# mainProbe_ESP12.net
KiCad netlist of a schematic drawn in EAGLE
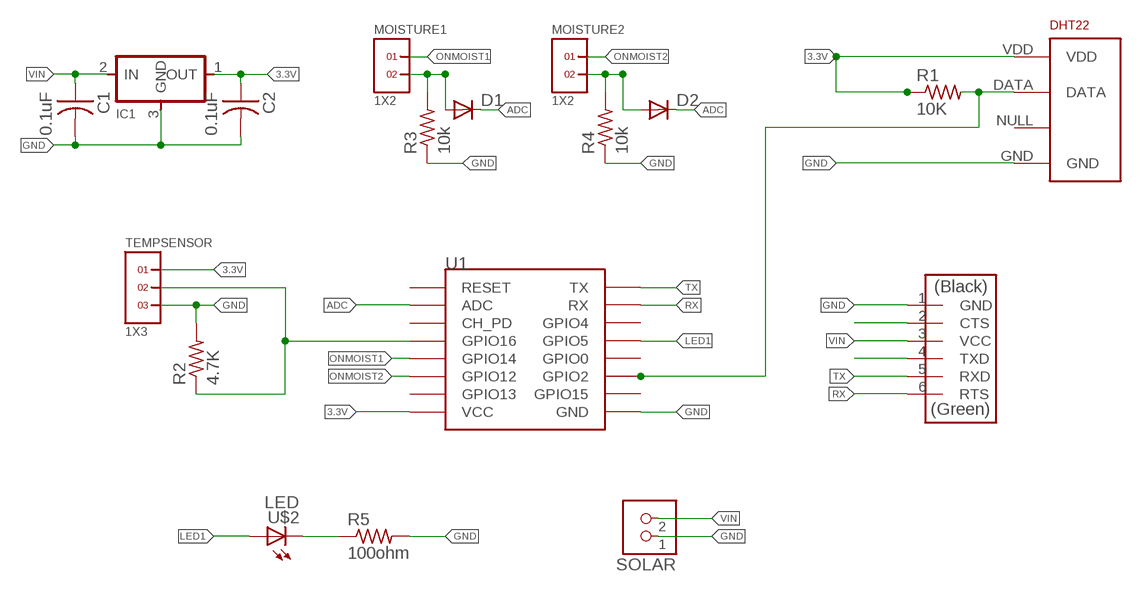
[diagram p0: schematic, sheet 1]

(export (version "E")
  (design (tool "Eeschema 10.0.6"))
  (components
    (comp (ref "C1")
      (value "0.1uF")
      (footprint "eagle-import:C1206")
      (libsource (lib "eagle-import") (part "CAP-US1206"))
    )
    (comp (ref "C2")
      (value "0.1uF")
      (footprint "eagle-import:C1206")
      (libsource (lib "eagle-import") (part "CAP-US1206"))
    )
    (comp (ref "D1")
      (value "DIODESOD123")
      (footprint "eagle-import:SOD123")
      (libsource (lib "eagle-import") (part "DIODESOD123"))
    )
    (comp (ref "D2")
      (value "DIODESOD123")
      (footprint "eagle-import:SOD123")
      (libsource (lib "eagle-import") (part "DIODESOD123"))
    )
    (comp (ref "DHT22")
      (value "RHT03_DHT-22_AM2302")
      (footprint "eagle-import:RHT03_DHT-22")
      (libsource (lib "eagle-import") (part "RHT03_DHT-22_AM2302"))
    )
    (comp (ref "IC1")
      (value "REGULATORSOT23")
      (footprint "eagle-import:SOT23")
      (libsource (lib "eagle-import") (part "REGULATORSOT23"))
    )
    (comp (ref "MOISTURE1")
      (value "1X2")
      (footprint "eagle-import:1X2")
      (libsource (lib "eagle-import") (part "1X2"))
    )
    (comp (ref "MOISTURE2")
      (value "1X2")
      (footprint "eagle-import:1X2")
      (libsource (lib "eagle-import") (part "1X2"))
    )
    (comp (ref "R1")
      (value "10K")
      (footprint "eagle-import:R1206")
      (libsource (lib "eagle-import") (part "RES-US1206"))
    )
    (comp (ref "R2")
      (value "4.7K")
      (footprint "eagle-import:R1206")
      (libsource (lib "eagle-import") (part "RES-US1206"))
    )
    (comp (ref "R3")
      (value "10k")
      (footprint "eagle-import:R1206")
      (libsource (lib "eagle-import") (part "RES-US1206"))
    )
    (comp (ref "R4")
      (value "10k")
      (footprint "eagle-import:R1206")
      (libsource (lib "eagle-import") (part "RES-US1206"))
    )
    (comp (ref "R5")
      (value "100ohm")
      (footprint "eagle-import:R1206")
      (libsource (lib "eagle-import") (part "RES-US1206"))
    )
    (comp (ref "SOLAR")
      (value "TERM-1X02-ADAFRUIT")
      (footprint "eagle-import:3.5MMTERM")
      (libsource (lib "eagle-import") (part "TERM-1X02-ADAFRUIT"))
    )
    (comp (ref "TEMPSENSOR")
      (value "1X3")
      (footprint "eagle-import:1X3")
      (libsource (lib "eagle-import") (part "1X3"))
    )
    (comp (ref "U$1")
      (value "FTDI-SMD-HEADER")
      (footprint "eagle-import:1X06SMD")
      (libsource (lib "eagle-import") (part "FTDI-SMD-HEADER"))
    )
    (comp (ref "U$2")
      (value "LED")
      (footprint "eagle-import:LED1206")
      (libsource (lib "eagle-import") (part "LED"))
    )
    (comp (ref "U1")
      (value "ESP12")
      (footprint "eagle-import:ESP12")
      (libsource (lib "eagle-import") (part "ESP12"))
    )
  )
  (nets
    (net (code "1") (name "3.3V") (class "Default")
      (node (ref "C2") (pin "1") (pinfunction "1_1") (pintype "passive"))
      (node (ref "DHT22") (pin "VDD") (pinfunction "VDD_VDD") (pintype "power_in"))
      (node (ref "IC1") (pin "1") (pinfunction "OUT_1") (pintype "bidirectional"))
      (node (ref "R1") (pin "1") (pinfunction "1_1") (pintype "passive"))
      (node (ref "TEMPSENSOR") (pin "1") (pinfunction "1_1") (pintype "bidirectional"))
      (node (ref "U1") (pin "VCC") (pinfunction "VCC_VCC") (pintype "bidirectional"))
    )
    (net (code "2") (name "ADC") (class "Default")
      (node (ref "D1") (pin "CATHODE") (pinfunction "C_CATHODE") (pintype "passive"))
      (node (ref "D2") (pin "CATHODE") (pinfunction "C_CATHODE") (pintype "passive"))
      (node (ref "U1") (pin "ADC") (pinfunction "ADC_ADC") (pintype "bidirectional"))
    )
    (net (code "3") (name "GND") (class "Default")
      (node (ref "C1") (pin "2") (pinfunction "2_2") (pintype "passive"))
      (node (ref "C2") (pin "2") (pinfunction "2_2") (pintype "passive"))
      (node (ref "DHT22") (pin "GND") (pinfunction "GND_GND") (pintype "power_in"))
      (node (ref "IC1") (pin "3") (pinfunction "GND_3") (pintype "bidirectional"))
      (node (ref "R2") (pin "2") (pinfunction "2_2") (pintype "passive"))
      (node (ref "R3") (pin "1") (pinfunction "1_1") (pintype "passive"))
      (node (ref "R4") (pin "1") (pinfunction "1_1") (pintype "passive"))
      (node (ref "R5") (pin "2") (pinfunction "2_2") (pintype "passive"))
      (node (ref "SOLAR") (pin "1") (pinfunction "1_1") (pintype "passive"))
      (node (ref "TEMPSENSOR") (pin "3") (pinfunction "3_3") (pintype "bidirectional"))
      (node (ref "U$1") (pin "1") (pinfunction "GND_1") (pintype "bidirectional"))
      (node (ref "U1") (pin "GND") (pinfunction "GND_GND") (pintype "bidirectional"))
    )
    (net (code "4") (name "LED1") (class "Default")
      (node (ref "U$2") (pin "1") (pinfunction "A_1") (pintype "passive"))
      (node (ref "U1") (pin "GPIO5") (pinfunction "GPIO5_GPIO5") (pintype "bidirectional"))
    )
    (net (code "5") (name "Net-(D1-A)") (class "Default")
      (node (ref "D1") (pin "ANODE") (pinfunction "A_ANODE") (pintype "passive"))
      (node (ref "MOISTURE1") (pin "2") (pinfunction "2_2") (pintype "bidirectional"))
      (node (ref "R3") (pin "2") (pinfunction "2_2") (pintype "passive"))
    )
    (net (code "6") (name "Net-(D2-A)") (class "Default")
      (node (ref "D2") (pin "ANODE") (pinfunction "A_ANODE") (pintype "passive"))
      (node (ref "MOISTURE2") (pin "2") (pinfunction "2_2") (pintype "bidirectional"))
      (node (ref "R4") (pin "2") (pinfunction "2_2") (pintype "passive"))
    )
    (net (code "7") (name "Net-(DHT22-PadDATA)") (class "Default")
      (node (ref "DHT22") (pin "DATA") (pinfunction "DATA_DATA") (pintype "bidirectional"))
      (node (ref "R1") (pin "2") (pinfunction "2_2") (pintype "passive"))
      (node (ref "U1") (pin "GPIO2") (pinfunction "GPIO2_GPIO2") (pintype "bidirectional"))
    )
    (net (code "8") (name "Net-(R2-Pad1)") (class "Default")
      (node (ref "R2") (pin "1") (pinfunction "1_1") (pintype "passive"))
      (node (ref "TEMPSENSOR") (pin "2") (pinfunction "2_2") (pintype "bidirectional"))
      (node (ref "U1") (pin "GPIO16") (pinfunction "GPIO16_GPIO16") (pintype "bidirectional"))
    )
    (net (code "9") (name "Net-(U$2-C)") (class "Default")
      (node (ref "R5") (pin "1") (pinfunction "1_1") (pintype "passive"))
      (node (ref "U$2") (pin "2") (pinfunction "C_2") (pintype "passive"))
    )
    (net (code "10") (name "ONMOIST1") (class "Default")
      (node (ref "MOISTURE1") (pin "1") (pinfunction "1_1") (pintype "bidirectional"))
      (node (ref "U1") (pin "GPIO14") (pinfunction "GPIO14_GPIO14") (pintype "bidirectional"))
    )
    (net (code "11") (name "ONMOIST2") (class "Default")
      (node (ref "MOISTURE2") (pin "1") (pinfunction "1_1") (pintype "bidirectional"))
      (node (ref "U1") (pin "GPIO12") (pinfunction "GPIO12_GPIO12") (pintype "bidirectional"))
    )
    (net (code "12") (name "RX") (class "Default")
      (node (ref "U$1") (pin "6") (pinfunction "RTS_6") (pintype "bidirectional"))
      (node (ref "U1") (pin "RX") (pinfunction "RX_RX") (pintype "bidirectional"))
    )
    (net (code "13") (name "TX") (class "Default")
      (node (ref "U$1") (pin "5") (pinfunction "RXD_5") (pintype "bidirectional"))
      (node (ref "U1") (pin "TX") (pinfunction "TX_TX") (pintype "bidirectional"))
    )
    (net (code "14") (name "VIN") (class "Default")
      (node (ref "C1") (pin "1") (pinfunction "1_1") (pintype "passive"))
      (node (ref "IC1") (pin "2") (pinfunction "IN_2") (pintype "bidirectional"))
      (node (ref "SOLAR") (pin "2") (pinfunction "2_2") (pintype "passive"))
      (node (ref "U$1") (pin "3") (pinfunction "VCC_3") (pintype "bidirectional"))
    )
    (net (code "15") (name "unconnected-(DHT22-PadNULL)") (class "Default")
      (node (ref "DHT22") (pin "NULL") (pinfunction "NULL_NULL") (pintype "no_connect"))
    )
    (net (code "16") (name "unconnected-(U$1-CTS-Pad2)") (class "Default")
      (node (ref "U$1") (pin "2") (pinfunction "CTS_2") (pintype "bidirectional"))
    )
    (net (code "17") (name "unconnected-(U$1-TXD-Pad4)") (class "Default")
      (node (ref "U$1") (pin "4") (pinfunction "TXD_4") (pintype "bidirectional"))
    )
    (net (code "18") (name "unconnected-(U1-PadCH_PD)") (class "Default")
      (node (ref "U1") (pin "CH_PD") (pinfunction "CH_PD_CH_PD") (pintype "bidirectional"))
    )
    (net (code "19") (name "unconnected-(U1-PadGPIO0)") (class "Default")
      (node (ref "U1") (pin "GPIO0") (pinfunction "GPIO0_GPIO0") (pintype "bidirectional"))
    )
    (net (code "20") (name "unconnected-(U1-PadGPIO4)") (class "Default")
      (node (ref "U1") (pin "GPIO4") (pinfunction "GPIO4_GPIO4") (pintype "bidirectional"))
    )
    (net (code "21") (name "unconnected-(U1-PadGPIO13)") (class "Default")
      (node (ref "U1") (pin "GPIO13") (pinfunction "GPIO13_GPIO13") (pintype "bidirectional"))
    )
    (net (code "22") (name "unconnected-(U1-PadGPIO15)") (class "Default")
      (node (ref "U1") (pin "GPIO15") (pinfunction "GPIO15_GPIO15") (pintype "bidirectional"))
    )
    (net (code "23") (name "unconnected-(U1-PadRESET)") (class "Default")
      (node (ref "U1") (pin "RESET") (pinfunction "RESET_RESET") (pintype "bidirectional"))
    )
  )
)
